# CtDPS_Stage.net
KiCad netlist of a schematic drawn in Altium Designer
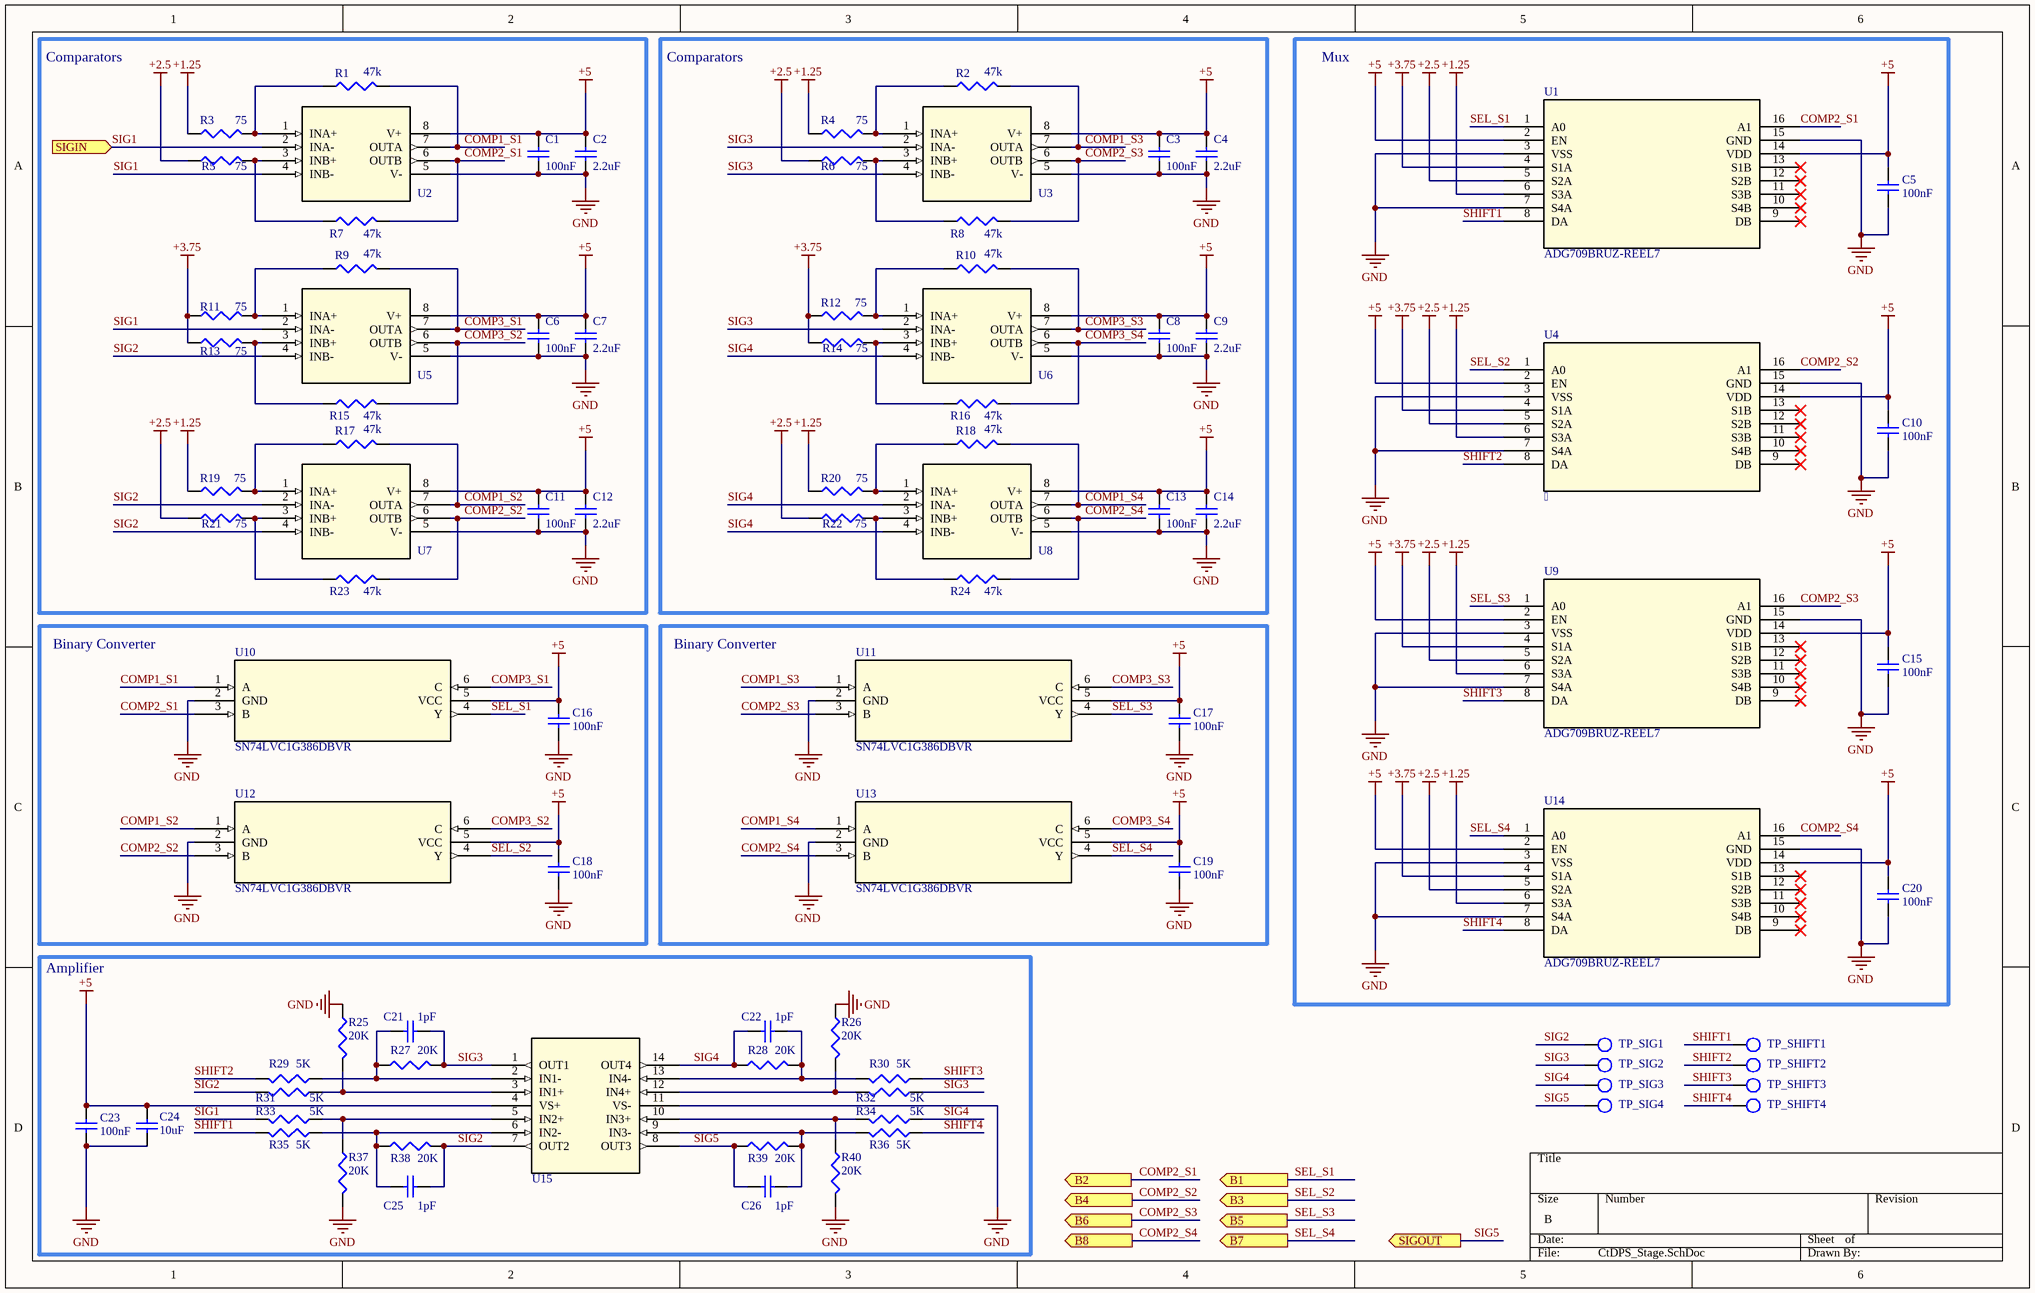
[diagram p0: CtDPS_Stage.SchDoc]

(export (version "E")
  (design (tool "Eeschema 10.0.6"))
  (components
    (comp (ref "C1")
      (value "100nF")
      (footprint "C_0402")
      (fields (field (name "LCSC PART #") "C1525"))
      (libsource (lib "ctdsp") (part "C_0402"))
    )
    (comp (ref "C2")
      (value "2.2uF")
      (footprint "C_0402")
      (fields (field (name "LCSC PART #") "C12530"))
      (libsource (lib "ctdsp") (part "C_0402"))
    )
    (comp (ref "C3")
      (value "100nF")
      (footprint "C_0402")
      (fields (field (name "LCSC PART #") "C1525"))
      (libsource (lib "ctdsp") (part "C_0402"))
    )
    (comp (ref "C4")
      (value "2.2uF")
      (footprint "C_0402")
      (fields (field (name "LCSC PART #") "C12530"))
      (libsource (lib "ctdsp") (part "C_0402"))
    )
    (comp (ref "C5")
      (value "100nF")
      (footprint "C_0402")
      (fields (field (name "LCSC PART #") "C1525"))
      (libsource (lib "ctdsp") (part "C_0402"))
    )
    (comp (ref "C6")
      (value "100nF")
      (footprint "C_0402")
      (fields (field (name "LCSC PART #") "C1525"))
      (libsource (lib "ctdsp") (part "C_0402"))
    )
    (comp (ref "C7")
      (value "2.2uF")
      (footprint "C_0402")
      (fields (field (name "LCSC PART #") "C12530"))
      (libsource (lib "ctdsp") (part "C_0402"))
    )
    (comp (ref "C8")
      (value "100nF")
      (footprint "C_0402")
      (fields (field (name "LCSC PART #") "C1525"))
      (libsource (lib "ctdsp") (part "C_0402"))
    )
    (comp (ref "C9")
      (value "2.2uF")
      (footprint "C_0402")
      (fields (field (name "LCSC PART #") "C12530"))
      (libsource (lib "ctdsp") (part "C_0402"))
    )
    (comp (ref "C10")
      (value "100nF")
      (footprint "C_0402")
      (fields (field (name "LCSC PART #") "C1525"))
      (libsource (lib "ctdsp") (part "C_0402"))
    )
    (comp (ref "C11")
      (value "100nF")
      (footprint "C_0402")
      (fields (field (name "LCSC PART #") "C1525"))
      (libsource (lib "ctdsp") (part "C_0402"))
    )
    (comp (ref "C12")
      (value "2.2uF")
      (footprint "C_0402")
      (fields (field (name "LCSC PART #") "C12530"))
      (libsource (lib "ctdsp") (part "C_0402"))
    )
    (comp (ref "C13")
      (value "100nF")
      (footprint "C_0402")
      (fields (field (name "LCSC PART #") "C1525"))
      (libsource (lib "ctdsp") (part "C_0402"))
    )
    (comp (ref "C14")
      (value "2.2uF")
      (footprint "C_0402")
      (fields (field (name "LCSC PART #") "C12530"))
      (libsource (lib "ctdsp") (part "C_0402"))
    )
    (comp (ref "C15")
      (value "100nF")
      (footprint "C_0402")
      (fields (field (name "LCSC PART #") "C1525"))
      (libsource (lib "ctdsp") (part "C_0402"))
    )
    (comp (ref "C16")
      (value "100nF")
      (footprint "C_0402")
      (fields (field (name "LCSC PART #") "C1525"))
      (libsource (lib "ctdsp") (part "C_0402"))
    )
    (comp (ref "C17")
      (value "100nF")
      (footprint "C_0402")
      (fields (field (name "LCSC PART #") "C1525"))
      (libsource (lib "ctdsp") (part "C_0402"))
    )
    (comp (ref "C18")
      (value "100nF")
      (footprint "C_0402")
      (fields (field (name "LCSC PART #") "C1525"))
      (libsource (lib "ctdsp") (part "C_0402"))
    )
    (comp (ref "C19")
      (value "100nF")
      (footprint "C_0402")
      (fields (field (name "LCSC PART #") "C1525"))
      (libsource (lib "ctdsp") (part "C_0402"))
    )
    (comp (ref "C20")
      (value "100nF")
      (footprint "C_0402")
      (fields (field (name "LCSC PART #") "C1525"))
      (libsource (lib "ctdsp") (part "C_0402"))
    )
    (comp (ref "C21")
      (value "1pF")
      (footprint "C_0402")
      (fields (field (name "LCSC PART #") "C1550"))
      (libsource (lib "ctdsp") (part "C_0402"))
    )
    (comp (ref "C22")
      (value "1pF")
      (footprint "C_0402")
      (fields (field (name "LCSC PART #") "C1550"))
      (libsource (lib "ctdsp") (part "C_0402"))
    )
    (comp (ref "C23")
      (value "100nF")
      (footprint "C_0402")
      (fields (field (name "LCSC PART #") "C1525"))
      (libsource (lib "ctdsp") (part "C_0402"))
    )
    (comp (ref "C24")
      (value "10uF")
      (footprint "C_0402")
      (fields (field (name "LCSC PART #") "C15525"))
      (libsource (lib "ctdsp") (part "C_0402"))
    )
    (comp (ref "C25")
      (value "1pF")
      (footprint "C_0402")
      (fields (field (name "LCSC PART #") "C1550"))
      (libsource (lib "ctdsp") (part "C_0402"))
    )
    (comp (ref "C26")
      (value "1pF")
      (footprint "C_0402")
      (fields (field (name "LCSC PART #") "C1550"))
      (libsource (lib "ctdsp") (part "C_0402"))
    )
    (comp (ref "R1")
      (value "47k")
      (footprint "RES_0603")
      (fields (field (name "LCSC PART #") "C25819"))
      (libsource (lib "ctdsp") (part "RES_0603"))
    )
    (comp (ref "R2")
      (value "47k")
      (footprint "RES_0603")
      (fields (field (name "LCSC PART #") "C25819"))
      (libsource (lib "ctdsp") (part "RES_0603"))
    )
    (comp (ref "R3")
      (value "75")
      (footprint "RES_0603")
      (fields (field (name "LCSC PART #") "C4275"))
      (libsource (lib "ctdsp") (part "RES_0603"))
    )
    (comp (ref "R4")
      (value "75")
      (footprint "RES_0603")
      (fields (field (name "LCSC PART #") "C4275"))
      (libsource (lib "ctdsp") (part "RES_0603"))
    )
    (comp (ref "R5")
      (value "75")
      (footprint "RES_0603")
      (fields (field (name "LCSC PART #") "C4275"))
      (libsource (lib "ctdsp") (part "RES_0603"))
    )
    (comp (ref "R6")
      (value "75")
      (footprint "RES_0603")
      (fields (field (name "LCSC PART #") "C4275"))
      (libsource (lib "ctdsp") (part "RES_0603"))
    )
    (comp (ref "R7")
      (value "47k")
      (footprint "RES_0603")
      (fields (field (name "LCSC PART #") "C25819"))
      (libsource (lib "ctdsp") (part "RES_0603"))
    )
    (comp (ref "R8")
      (value "47k")
      (footprint "RES_0603")
      (fields (field (name "LCSC PART #") "C25819"))
      (libsource (lib "ctdsp") (part "RES_0603"))
    )
    (comp (ref "R9")
      (value "47k")
      (footprint "RES_0603")
      (fields (field (name "LCSC PART #") "C25819"))
      (libsource (lib "ctdsp") (part "RES_0603"))
    )
    (comp (ref "R10")
      (value "47k")
      (footprint "RES_0603")
      (fields (field (name "LCSC PART #") "C25819"))
      (libsource (lib "ctdsp") (part "RES_0603"))
    )
    (comp (ref "R11")
      (value "75")
      (footprint "RES_0603")
      (fields (field (name "LCSC PART #") "C4275"))
      (libsource (lib "ctdsp") (part "RES_0603"))
    )
    (comp (ref "R12")
      (value "75")
      (footprint "RES_0603")
      (fields (field (name "LCSC PART #") "C4275"))
      (libsource (lib "ctdsp") (part "RES_0603"))
    )
    (comp (ref "R13")
      (value "75")
      (footprint "RES_0603")
      (fields (field (name "LCSC PART #") "C4275"))
      (libsource (lib "ctdsp") (part "RES_0603"))
    )
    (comp (ref "R14")
      (value "75")
      (footprint "RES_0603")
      (fields (field (name "LCSC PART #") "C4275"))
      (libsource (lib "ctdsp") (part "RES_0603"))
    )
    (comp (ref "R15")
      (value "47k")
      (footprint "RES_0603")
      (fields (field (name "LCSC PART #") "C25819"))
      (libsource (lib "ctdsp") (part "RES_0603"))
    )
    (comp (ref "R16")
      (value "47k")
      (footprint "RES_0603")
      (fields (field (name "LCSC PART #") "C25819"))
      (libsource (lib "ctdsp") (part "RES_0603"))
    )
    (comp (ref "R17")
      (value "47k")
      (footprint "RES_0603")
      (fields (field (name "LCSC PART #") "C25819"))
      (libsource (lib "ctdsp") (part "RES_0603"))
    )
    (comp (ref "R18")
      (value "47k")
      (footprint "RES_0603")
      (fields (field (name "LCSC PART #") "C25819"))
      (libsource (lib "ctdsp") (part "RES_0603"))
    )
    (comp (ref "R19")
      (value "75")
      (footprint "RES_0603")
      (fields (field (name "LCSC PART #") "C4275"))
      (libsource (lib "ctdsp") (part "RES_0603"))
    )
    (comp (ref "R20")
      (value "75")
      (footprint "RES_0603")
      (fields (field (name "LCSC PART #") "C4275"))
      (libsource (lib "ctdsp") (part "RES_0603"))
    )
    (comp (ref "R21")
      (value "75")
      (footprint "RES_0603")
      (fields (field (name "LCSC PART #") "C4275"))
      (libsource (lib "ctdsp") (part "RES_0603"))
    )
    (comp (ref "R22")
      (value "75")
      (footprint "RES_0603")
      (fields (field (name "LCSC PART #") "C4275"))
      (libsource (lib "ctdsp") (part "RES_0603"))
    )
    (comp (ref "R23")
      (value "47k")
      (footprint "RES_0603")
      (fields (field (name "LCSC PART #") "C25819"))
      (libsource (lib "ctdsp") (part "RES_0603"))
    )
    (comp (ref "R24")
      (value "47k")
      (footprint "RES_0603")
      (fields (field (name "LCSC PART #") "C25819"))
      (libsource (lib "ctdsp") (part "RES_0603"))
    )
    (comp (ref "R25")
      (value "20K")
      (footprint "RES_0402")
      (fields (field (name "LCSC PART #") "C25765"))
      (libsource (lib "ctdsp") (part "RES_0402"))
    )
    (comp (ref "R26")
      (value "20K")
      (footprint "RES_0402")
      (fields (field (name "LCSC PART #") "C25765"))
      (libsource (lib "ctdsp") (part "RES_0402"))
    )
    (comp (ref "R27")
      (value "20K")
      (footprint "RES_0402")
      (fields (field (name "LCSC PART #") "C25765"))
      (libsource (lib "ctdsp") (part "RES_0402"))
    )
    (comp (ref "R28")
      (value "20K")
      (footprint "RES_0402")
      (fields (field (name "LCSC PART #") "C25765"))
      (libsource (lib "ctdsp") (part "RES_0402"))
    )
    (comp (ref "R29")
      (value "5K")
      (footprint "RES_0402")
      (fields (field (name "LCSC PART #") "C5948099"))
      (libsource (lib "ctdsp") (part "RES_0402"))
    )
    (comp (ref "R30")
      (value "5K")
      (footprint "RES_0402")
      (fields (field (name "LCSC PART #") "C5948099"))
      (libsource (lib "ctdsp") (part "RES_0402"))
    )
    (comp (ref "R31")
      (value "5K")
      (footprint "RES_0402")
      (fields (field (name "LCSC PART #") "C5948099"))
      (libsource (lib "ctdsp") (part "RES_0402"))
    )
    (comp (ref "R32")
      (value "5K")
      (footprint "RES_0402")
      (fields (field (name "LCSC PART #") "C5948099"))
      (libsource (lib "ctdsp") (part "RES_0402"))
    )
    (comp (ref "R33")
      (value "5K")
      (footprint "RES_0402")
      (fields (field (name "LCSC PART #") "C5948099"))
      (libsource (lib "ctdsp") (part "RES_0402"))
    )
    (comp (ref "R34")
      (value "5K")
      (footprint "RES_0402")
      (fields (field (name "LCSC PART #") "C5948099"))
      (libsource (lib "ctdsp") (part "RES_0402"))
    )
    (comp (ref "R35")
      (value "5K")
      (footprint "RES_0402")
      (fields (field (name "LCSC PART #") "C5948099"))
      (libsource (lib "ctdsp") (part "RES_0402"))
    )
    (comp (ref "R36")
      (value "5K")
      (footprint "RES_0402")
      (fields (field (name "LCSC PART #") "C5948099"))
      (libsource (lib "ctdsp") (part "RES_0402"))
    )
    (comp (ref "R37")
      (value "20K")
      (footprint "RES_0402")
      (fields (field (name "LCSC PART #") "C25765"))
      (libsource (lib "ctdsp") (part "RES_0402"))
    )
    (comp (ref "R38")
      (value "20K")
      (footprint "RES_0402")
      (fields (field (name "LCSC PART #") "C25765"))
      (libsource (lib "ctdsp") (part "RES_0402"))
    )
    (comp (ref "R39")
      (value "20K")
      (footprint "RES_0402")
      (fields (field (name "LCSC PART #") "C25765"))
      (libsource (lib "ctdsp") (part "RES_0402"))
    )
    (comp (ref "R40")
      (value "20K")
      (footprint "RES_0402")
      (fields (field (name "LCSC PART #") "C25765"))
      (libsource (lib "ctdsp") (part "RES_0402"))
    )
    (comp (ref "TP_SHIFT1")
      (value "TESTPOINT")
      (footprint "TESTPOINT")
      (libsource (lib "ctdsp") (part "TESTPOINT"))
    )
    (comp (ref "TP_SHIFT2")
      (value "TESTPOINT")
      (footprint "TESTPOINT")
      (libsource (lib "ctdsp") (part "TESTPOINT"))
    )
    (comp (ref "TP_SHIFT3")
      (value "TESTPOINT")
      (footprint "TESTPOINT")
      (libsource (lib "ctdsp") (part "TESTPOINT"))
    )
    (comp (ref "TP_SHIFT4")
      (value "TESTPOINT")
      (footprint "TESTPOINT")
      (libsource (lib "ctdsp") (part "TESTPOINT"))
    )
    (comp (ref "TP_SIG1")
      (value "TESTPOINT")
      (footprint "TESTPOINT")
      (libsource (lib "ctdsp") (part "TESTPOINT"))
    )
    (comp (ref "TP_SIG2")
      (value "TESTPOINT")
      (footprint "TESTPOINT")
      (libsource (lib "ctdsp") (part "TESTPOINT"))
    )
    (comp (ref "TP_SIG3")
      (value "TESTPOINT")
      (footprint "TESTPOINT")
      (libsource (lib "ctdsp") (part "TESTPOINT"))
    )
    (comp (ref "TP_SIG4")
      (value "TESTPOINT")
      (footprint "TESTPOINT")
      (libsource (lib "ctdsp") (part "TESTPOINT"))
    )
    (comp (ref "U1")
      (value "ADG709BRUZ-REEL7")
      (footprint "ADG709BRUZ-REEL7")
      (description "CMOS Low Voltage, 3 Î© 4-Channel Multiplexer")
      (fields (field (name "LCSC PART #") "C206785"))
      (libsource (lib "ctdsp") (part "ADG709BRUZ-REEL7"))
    )
    (comp (ref "U2")
      (value "TLV3502AIDR")
      (footprint "TLV3502AIDR")
      (description "Dual 4.5ns Push-pull Rail-to-Rail Input, Rail-to-Rail Output TTL Comparators")
      (fields (field (name "LCSC PART #") "C131165"))
      (libsource (lib "ctdsp") (part "TLV3502AIDR"))
    )
    (comp (ref "U3")
      (value "TLV3502AIDR")
      (footprint "TLV3502AIDR")
      (description "Dual 4.5ns Push-pull Rail-to-Rail Input, Rail-to-Rail Output TTL Comparators")
      (fields (field (name "LCSC PART #") "C131165"))
      (libsource (lib "ctdsp") (part "TLV3502AIDR"))
    )
    (comp (ref "U4")
      (value "")
      (footprint "ADG709BRUZ-REEL7")
      (description "CMOS Low Voltage, 3 Î© 4-Channel Multiplexer")
      (fields (field (name "LCSC PART #") "C206785"))
      (libsource (lib "ctdsp") (part "ADG709BRUZ-REEL7"))
    )
    (comp (ref "U5")
      (value "TLV3502AIDR")
      (footprint "TLV3502AIDR")
      (description "Dual 4.5ns Push-pull Rail-to-Rail Input, Rail-to-Rail Output TTL Comparators")
      (fields (field (name "LCSC PART #") "C131165"))
      (libsource (lib "ctdsp") (part "TLV3502AIDR"))
    )
    (comp (ref "U6")
      (value "TLV3502AIDR")
      (footprint "TLV3502AIDR")
      (description "Dual 4.5ns Push-pull Rail-to-Rail Input, Rail-to-Rail Output TTL Comparators")
      (fields (field (name "LCSC PART #") "C131165"))
      (libsource (lib "ctdsp") (part "TLV3502AIDR"))
    )
    (comp (ref "U7")
      (value "TLV3502AIDR")
      (footprint "TLV3502AIDR")
      (description "Dual 4.5ns Push-pull Rail-to-Rail Input, Rail-to-Rail Output TTL Comparators")
      (fields (field (name "LCSC PART #") "C131165"))
      (libsource (lib "ctdsp") (part "TLV3502AIDR"))
    )
    (comp (ref "U8")
      (value "TLV3502AIDR")
      (footprint "TLV3502AIDR")
      (description "Dual 4.5ns Push-pull Rail-to-Rail Input, Rail-to-Rail Output TTL Comparators")
      (fields (field (name "LCSC PART #") "C131165"))
      (libsource (lib "ctdsp") (part "TLV3502AIDR"))
    )
    (comp (ref "U9")
      (value "ADG709BRUZ-REEL7")
      (footprint "ADG709BRUZ-REEL7")
      (description "CMOS Low Voltage, 3 Î© 4-Channel Multiplexer")
      (fields (field (name "LCSC PART #") "C206785"))
      (libsource (lib "ctdsp") (part "ADG709BRUZ-REEL7"))
    )
    (comp (ref "U10")
      (value "SN74LVC1G386DBVR")
      (footprint "SN74LVC1G386DBVR")
      (description "Single 3-input, 1.65-V to 5.5-V XOR (exclusive OR) gate 6-SOT-23 -40 to 125")
      (fields (field (name "LCSC PART #") "C2838503"))
      (libsource (lib "ctdsp") (part "SN74LVC1G386DBVR"))
    )
    (comp (ref "U11")
      (value "SN74LVC1G386DBVR")
      (footprint "SN74LVC1G386DBVR")
      (description "Single 3-input, 1.65-V to 5.5-V XOR (exclusive OR) gate 6-SOT-23 -40 to 125")
      (fields (field (name "LCSC PART #") "C2838503"))
      (libsource (lib "ctdsp") (part "SN74LVC1G386DBVR"))
    )
    (comp (ref "U12")
      (value "SN74LVC1G386DBVR")
      (footprint "SN74LVC1G386DBVR")
      (description "Single 3-input, 1.65-V to 5.5-V XOR (exclusive OR) gate 6-SOT-23 -40 to 125")
      (fields (field (name "LCSC PART #") "C2838503"))
      (libsource (lib "ctdsp") (part "SN74LVC1G386DBVR"))
    )
    (comp (ref "U13")
      (value "SN74LVC1G386DBVR")
      (footprint "SN74LVC1G386DBVR")
      (description "Single 3-input, 1.65-V to 5.5-V XOR (exclusive OR) gate 6-SOT-23 -40 to 125")
      (fields (field (name "LCSC PART #") "C2838503"))
      (libsource (lib "ctdsp") (part "SN74LVC1G386DBVR"))
    )
    (comp (ref "U14")
      (value "ADG709BRUZ-REEL7")
      (footprint "ADG709BRUZ-REEL7")
      (description "CMOS Low Voltage, 3 Î© 4-Channel Multiplexer")
      (fields (field (name "LCSC PART #") "C206785"))
      (libsource (lib "ctdsp") (part "ADG709BRUZ-REEL7"))
    )
    (comp (ref "U15")
      (value "ADA4891-4ARZ-R7")
      (footprint "ADA4891-4ARZ-R7")
      (description "Quad Rail-to-Rail Op-Amp, 240 MHz, 170 V/µs, SOT-23-5")
      (fields (field (name "LCSC PART #") "C654290"))
      (libsource (lib "ctdsp") (part "ADA4891-4ARZ-R7"))
    )
  )
  (nets
    (net (code "1") (name "+1.25") (class "Default")
      (node (ref "R19") (pin "1") (pinfunction "1_1") (pintype "passive"))
      (node (ref "R20") (pin "1") (pinfunction "1_1") (pintype "passive"))
      (node (ref "R3") (pin "1") (pinfunction "1_1") (pintype "passive"))
      (node (ref "R4") (pin "1") (pinfunction "1_1") (pintype "passive"))
      (node (ref "U1") (pin "6") (pinfunction "S3A_6") (pintype "passive"))
      (node (ref "U14") (pin "6") (pinfunction "S3A_6") (pintype "passive"))
      (node (ref "U4") (pin "6") (pinfunction "S3A_6") (pintype "passive"))
      (node (ref "U9") (pin "6") (pinfunction "S3A_6") (pintype "passive"))
    )
    (net (code "2") (name "+2.5") (class "Default")
      (node (ref "R21") (pin "1") (pinfunction "1_1") (pintype "passive"))
      (node (ref "R22") (pin "1") (pinfunction "1_1") (pintype "passive"))
      (node (ref "R5") (pin "1") (pinfunction "1_1") (pintype "passive"))
      (node (ref "R6") (pin "1") (pinfunction "1_1") (pintype "passive"))
      (node (ref "U1") (pin "5") (pinfunction "S2A_5") (pintype "passive"))
      (node (ref "U14") (pin "5") (pinfunction "S2A_5") (pintype "passive"))
      (node (ref "U4") (pin "5") (pinfunction "S2A_5") (pintype "passive"))
      (node (ref "U9") (pin "5") (pinfunction "S2A_5") (pintype "passive"))
    )
    (net (code "3") (name "+3.75") (class "Default")
      (node (ref "R11") (pin "1") (pinfunction "1_1") (pintype "passive"))
      (node (ref "R12") (pin "1") (pinfunction "1_1") (pintype "passive"))
      (node (ref "R13") (pin "1") (pinfunction "1_1") (pintype "passive"))
      (node (ref "R14") (pin "1") (pinfunction "1_1") (pintype "passive"))
      (node (ref "U1") (pin "4") (pinfunction "S1A_4") (pintype "passive"))
      (node (ref "U14") (pin "4") (pinfunction "S1A_4") (pintype "passive"))
      (node (ref "U4") (pin "4") (pinfunction "S1A_4") (pintype "passive"))
      (node (ref "U9") (pin "4") (pinfunction "S1A_4") (pintype "passive"))
    )
    (net (code "4") (name "+5") (class "Default")
      (node (ref "C1") (pin "1") (pinfunction "1_1") (pintype "passive"))
      (node (ref "C10") (pin "1") (pinfunction "1_1") (pintype "passive"))
      (node (ref "C11") (pin "1") (pinfunction "1_1") (pintype "passive"))
      (node (ref "C12") (pin "2") (pinfunction "2_2") (pintype "passive"))
      (node (ref "C13") (pin "1") (pinfunction "1_1") (pintype "passive"))
      (node (ref "C14") (pin "2") (pinfunction "2_2") (pintype "passive"))
      (node (ref "C15") (pin "1") (pinfunction "1_1") (pintype "passive"))
      (node (ref "C16") (pin "1") (pinfunction "1_1") (pintype "passive"))
      (node (ref "C17") (pin "1") (pinfunction "1_1") (pintype "passive"))
      (node (ref "C18") (pin "1") (pinfunction "1_1") (pintype "passive"))
      (node (ref "C19") (pin "1") (pinfunction "1_1") (pintype "passive"))
      (node (ref "C2") (pin "2") (pinfunction "2_2") (pintype "passive"))
      (node (ref "C20") (pin "1") (pinfunction "1_1") (pintype "passive"))
      (node (ref "C23") (pin "1") (pinfunction "1_1") (pintype "passive"))
      (node (ref "C24") (pin "2") (pinfunction "2_2") (pintype "passive"))
      (node (ref "C3") (pin "1") (pinfunction "1_1") (pintype "passive"))
      (node (ref "C4") (pin "2") (pinfunction "2_2") (pintype "passive"))
      (node (ref "C5") (pin "1") (pinfunction "1_1") (pintype "passive"))
      (node (ref "C6") (pin "1") (pinfunction "1_1") (pintype "passive"))
      (node (ref "C7") (pin "2") (pinfunction "2_2") (pintype "passive"))
      (node (ref "C8") (pin "1") (pinfunction "1_1") (pintype "passive"))
      (node (ref "C9") (pin "2") (pinfunction "2_2") (pintype "passive"))
      (node (ref "U1") (pin "14") (pinfunction "VDD_14") (pintype "power_in"))
      (node (ref "U1") (pin "2") (pinfunction "EN_2") (pintype "passive"))
      (node (ref "U10") (pin "5") (pinfunction "VCC_5") (pintype "power_in"))
      (node (ref "U11") (pin "5") (pinfunction "VCC_5") (pintype "power_in"))
      (node (ref "U12") (pin "5") (pinfunction "VCC_5") (pintype "power_in"))
      (node (ref "U13") (pin "5") (pinfunction "VCC_5") (pintype "power_in"))
      (node (ref "U14") (pin "14") (pinfunction "VDD_14") (pintype "power_in"))
      (node (ref "U14") (pin "2") (pinfunction "EN_2") (pintype "passive"))
      (node (ref "U15") (pin "4") (pinfunction "VS+_4") (pintype "power_in"))
      (node (ref "U2") (pin "8") (pinfunction "V+_8") (pintype "power_in"))
      (node (ref "U3") (pin "8") (pinfunction "V+_8") (pintype "power_in"))
      (node (ref "U4") (pin "14") (pinfunction "VDD_14") (pintype "power_in"))
      (node (ref "U4") (pin "2") (pinfunction "EN_2") (pintype "passive"))
      (node (ref "U5") (pin "8") (pinfunction "V+_8") (pintype "power_in"))
      (node (ref "U6") (pin "8") (pinfunction "V+_8") (pintype "power_in"))
      (node (ref "U7") (pin "8") (pinfunction "V+_8") (pintype "power_in"))
      (node (ref "U8") (pin "8") (pinfunction "V+_8") (pintype "power_in"))
      (node (ref "U9") (pin "14") (pinfunction "VDD_14") (pintype "power_in"))
      (node (ref "U9") (pin "2") (pinfunction "EN_2") (pintype "passive"))
    )
    (net (code "5") (name "/COMP1_S1") (class "Default")
      (node (ref "R1") (pin "2") (pinfunction "2_2") (pintype "passive"))
      (node (ref "U10") (pin "1") (pinfunction "A_1") (pintype "input"))
      (node (ref "U2") (pin "7") (pinfunction "OUTA_7") (pintype "output"))
    )
    (net (code "6") (name "/COMP1_S2") (class "Default")
      (node (ref "R17") (pin "2") (pinfunction "2_2") (pintype "passive"))
      (node (ref "U12") (pin "1") (pinfunction "A_1") (pintype "input"))
      (node (ref "U7") (pin "7") (pinfunction "OUTA_7") (pintype "output"))
    )
    (net (code "7") (name "/COMP1_S3") (class "Default")
      (node (ref "R2") (pin "2") (pinfunction "2_2") (pintype "passive"))
      (node (ref "U11") (pin "1") (pinfunction "A_1") (pintype "input"))
      (node (ref "U3") (pin "7") (pinfunction "OUTA_7") (pintype "output"))
    )
    (net (code "8") (name "/COMP1_S4") (class "Default")
      (node (ref "R18") (pin "2") (pinfunction "2_2") (pintype "passive"))
      (node (ref "U13") (pin "1") (pinfunction "A_1") (pintype "input"))
      (node (ref "U8") (pin "7") (pinfunction "OUTA_7") (pintype "output"))
    )
    (net (code "9") (name "/COMP2_S1") (class "Default")
      (node (ref "R7") (pin "2") (pinfunction "2_2") (pintype "passive"))
      (node (ref "U1") (pin "16") (pinfunction "A1_16") (pintype "passive"))
      (node (ref "U10") (pin "3") (pinfunction "B_3") (pintype "input"))
      (node (ref "U2") (pin "6") (pinfunction "OUTB_6") (pintype "output"))
    )
    (net (code "10") (name "/COMP2_S2") (class "Default")
      (node (ref "R23") (pin "2") (pinfunction "2_2") (pintype "passive"))
      (node (ref "U12") (pin "3") (pinfunction "B_3") (pintype "input"))
      (node (ref "U4") (pin "16") (pinfunction "A1_16") (pintype "passive"))
      (node (ref "U7") (pin "6") (pinfunction "OUTB_6") (pintype "output"))
    )
    (net (code "11") (name "/COMP2_S3") (class "Default")
      (node (ref "R8") (pin "2") (pinfunction "2_2") (pintype "passive"))
      (node (ref "U11") (pin "3") (pinfunction "B_3") (pintype "input"))
      (node (ref "U3") (pin "6") (pinfunction "OUTB_6") (pintype "output"))
      (node (ref "U9") (pin "16") (pinfunction "A1_16") (pintype "passive"))
    )
    (net (code "12") (name "/COMP2_S4") (class "Default")
      (node (ref "R24") (pin "2") (pinfunction "2_2") (pintype "passive"))
      (node (ref "U13") (pin "3") (pinfunction "B_3") (pintype "input"))
      (node (ref "U14") (pin "16") (pinfunction "A1_16") (pintype "passive"))
      (node (ref "U8") (pin "6") (pinfunction "OUTB_6") (pintype "output"))
    )
    (net (code "13") (name "/COMP3_S1") (class "Default")
      (node (ref "R9") (pin "2") (pinfunction "2_2") (pintype "passive"))
      (node (ref "U10") (pin "6") (pinfunction "C_6") (pintype "input"))
      (node (ref "U5") (pin "7") (pinfunction "OUTA_7") (pintype "output"))
    )
    (net (code "14") (name "/COMP3_S2") (class "Default")
      (node (ref "R15") (pin "2") (pinfunction "2_2") (pintype "passive"))
      (node (ref "U12") (pin "6") (pinfunction "C_6") (pintype "input"))
      (node (ref "U5") (pin "6") (pinfunction "OUTB_6") (pintype "output"))
    )
    (net (code "15") (name "/COMP3_S3") (class "Default")
      (node (ref "R10") (pin "2") (pinfunction "2_2") (pintype "passive"))
      (node (ref "U11") (pin "6") (pinfunction "C_6") (pintype "input"))
      (node (ref "U6") (pin "7") (pinfunction "OUTA_7") (pintype "output"))
    )
    (net (code "16") (name "/COMP3_S4") (class "Default")
      (node (ref "R16") (pin "2") (pinfunction "2_2") (pintype "passive"))
      (node (ref "U13") (pin "6") (pinfunction "C_6") (pintype "input"))
      (node (ref "U6") (pin "6") (pinfunction "OUTB_6") (pintype "output"))
    )
    (net (code "17") (name "/SEL_S1") (class "Default")
      (node (ref "U1") (pin "1") (pinfunction "A0_1") (pintype "passive"))
      (node (ref "U10") (pin "4") (pinfunction "Y_4") (pintype "output"))
    )
    (net (code "18") (name "/SEL_S2") (class "Default")
      (node (ref "U12") (pin "4") (pinfunction "Y_4") (pintype "output"))
      (node (ref "U4") (pin "1") (pinfunction "A0_1") (pintype "passive"))
    )
    (net (code "19") (name "/SEL_S3") (class "Default")
      (node (ref "U11") (pin "4") (pinfunction "Y_4") (pintype "output"))
      (node (ref "U9") (pin "1") (pinfunction "A0_1") (pintype "passive"))
    )
    (net (code "20") (name "/SEL_S4") (class "Default")
      (node (ref "U13") (pin "4") (pinfunction "Y_4") (pintype "output"))
      (node (ref "U14") (pin "1") (pinfunction "A0_1") (pintype "passive"))
    )
    (net (code "21") (name "/SHIFT1") (class "Default")
      (node (ref "R35") (pin "1") (pinfunction "1_1") (pintype "passive"))
      (node (ref "TP_SHIFT1") (pin "1") (pinfunction "1_1") (pintype "passive"))
      (node (ref "U1") (pin "8") (pinfunction "DA_8") (pintype "passive"))
    )
    (net (code "22") (name "/SHIFT2") (class "Default")
      (node (ref "R29") (pin "1") (pinfunction "1_1") (pintype "passive"))
      (node (ref "TP_SHIFT2") (pin "1") (pinfunction "1_1") (pintype "passive"))
      (node (ref "U4") (pin "8") (pinfunction "DA_8") (pintype "passive"))
    )
    (net (code "23") (name "/SHIFT3") (class "Default")
      (node (ref "R30") (pin "2") (pinfunction "2_2") (pintype "passive"))
      (node (ref "TP_SHIFT3") (pin "1") (pinfunction "1_1") (pintype "passive"))
      (node (ref "U9") (pin "8") (pinfunction "DA_8") (pintype "passive"))
    )
    (net (code "24") (name "/SHIFT4") (class "Default")
      (node (ref "R36") (pin "2") (pinfunction "2_2") (pintype "passive"))
      (node (ref "TP_SHIFT4") (pin "1") (pinfunction "1_1") (pintype "passive"))
      (node (ref "U14") (pin "8") (pinfunction "DA_8") (pintype "passive"))
    )
    (net (code "25") (name "/SIG1") (class "Default")
      (node (ref "R33") (pin "1") (pinfunction "1_1") (pintype "passive"))
      (node (ref "U2") (pin "2") (pinfunction "INA-_2") (pintype "input"))
      (node (ref "U2") (pin "4") (pinfunction "INB-_4") (pintype "input"))
      (node (ref "U5") (pin "2") (pinfunction "INA-_2") (pintype "input"))
    )
    (net (code "26") (name "/SIG2") (class "Default")
      (node (ref "C25") (pin "2") (pinfunction "2_2") (pintype "passive"))
      (node (ref "R31") (pin "1") (pinfunction "1_1") (pintype "passive"))
      (node (ref "R38") (pin "2") (pinfunction "2_2") (pintype "passive"))
      (node (ref "TP_SIG1") (pin "1") (pinfunction "1_1") (pintype "passive"))
      (node (ref "U15") (pin "7") (pinfunction "OUT2_7") (pintype "output"))
      (node (ref "U5") (pin "4") (pinfunction "INB-_4") (pintype "input"))
      (node (ref "U7") (pin "2") (pinfunction "INA-_2") (pintype "input"))
      (node (ref "U7") (pin "4") (pinfunction "INB-_4") (pintype "input"))
    )
    (net (code "27") (name "/SIG3") (class "Default")
      (node (ref "C21") (pin "2") (pinfunction "2_2") (pintype "passive"))
      (node (ref "R27") (pin "2") (pinfunction "2_2") (pintype "passive"))
      (node (ref "R32") (pin "2") (pinfunction "2_2") (pintype "passive"))
      (node (ref "TP_SIG2") (pin "1") (pinfunction "1_1") (pintype "passive"))
      (node (ref "U15") (pin "1") (pinfunction "OUT1_1") (pintype "output"))
      (node (ref "U3") (pin "2") (pinfunction "INA-_2") (pintype "input"))
      (node (ref "U3") (pin "4") (pinfunction "INB-_4") (pintype "input"))
      (node (ref "U6") (pin "2") (pinfunction "INA-_2") (pintype "input"))
    )
    (net (code "28") (name "/SIG4") (class "Default")
      (node (ref "C22") (pin "1") (pinfunction "1_1") (pintype "passive"))
      (node (ref "R28") (pin "1") (pinfunction "1_1") (pintype "passive"))
      (node (ref "R34") (pin "2") (pinfunction "2_2") (pintype "passive"))
      (node (ref "TP_SIG3") (pin "1") (pinfunction "1_1") (pintype "passive"))
      (node (ref "U15") (pin "14") (pinfunction "OUT4_14") (pintype "output"))
      (node (ref "U6") (pin "4") (pinfunction "INB-_4") (pintype "input"))
      (node (ref "U8") (pin "2") (pinfunction "INA-_2") (pintype "input"))
      (node (ref "U8") (pin "4") (pinfunction "INB-_4") (pintype "input"))
    )
    (net (code "29") (name "/SIG5") (class "Default")
      (node (ref "C26") (pin "1") (pinfunction "1_1") (pintype "passive"))
      (node (ref "R39") (pin "1") (pinfunction "1_1") (pintype "passive"))
      (node (ref "TP_SIG4") (pin "1") (pinfunction "1_1") (pintype "passive"))
      (node (ref "U15") (pin "8") (pinfunction "OUT3_8") (pintype "output"))
    )
    (net (code "30") (name "GND") (class "Default")
      (node (ref "C1") (pin "2") (pinfunction "2_2") (pintype "passive"))
      (node (ref "C10") (pin "2") (pinfunction "2_2") (pintype "passive"))
      (node (ref "C11") (pin "2") (pinfunction "2_2") (pintype "passive"))
      (node (ref "C12") (pin "1") (pinfunction "1_1") (pintype "passive"))
      (node (ref "C13") (pin "2") (pinfunction "2_2") (pintype "passive"))
      (node (ref "C14") (pin "1") (pinfunction "1_1") (pintype "passive"))
      (node (ref "C15") (pin "2") (pinfunction "2_2") (pintype "passive"))
      (node (ref "C16") (pin "2") (pinfunction "2_2") (pintype "passive"))
      (node (ref "C17") (pin "2") (pinfunction "2_2") (pintype "passive"))
      (node (ref "C18") (pin "2") (pinfunction "2_2") (pintype "passive"))
      (node (ref "C19") (pin "2") (pinfunction "2_2") (pintype "passive"))
      (node (ref "C2") (pin "1") (pinfunction "1_1") (pintype "passive"))
      (node (ref "C20") (pin "2") (pinfunction "2_2") (pintype "passive"))
      (node (ref "C23") (pin "2") (pinfunction "2_2") (pintype "passive"))
      (node (ref "C24") (pin "1") (pinfunction "1_1") (pintype "passive"))
      (node (ref "C3") (pin "2") (pinfunction "2_2") (pintype "passive"))
      (node (ref "C4") (pin "1") (pinfunction "1_1") (pintype "passive"))
      (node (ref "C5") (pin "2") (pinfunction "2_2") (pintype "passive"))
      (node (ref "C6") (pin "2") (pinfunction "2_2") (pintype "passive"))
      (node (ref "C7") (pin "1") (pinfunction "1_1") (pintype "passive"))
      (node (ref "C8") (pin "2") (pinfunction "2_2") (pintype "passive"))
      (node (ref "C9") (pin "1") (pinfunction "1_1") (pintype "passive"))
      (node (ref "R25") (pin "1") (pinfunction "1_1") (pintype "passive"))
      (node (ref "R26") (pin "1") (pinfunction "1_1") (pintype "passive"))
      (node (ref "R37") (pin "2") (pinfunction "2_2") (pintype "passive"))
      (node (ref "R40") (pin "2") (pinfunction "2_2") (pintype "passive"))
      (node (ref "U1") (pin "15") (pinfunction "GND_15") (pintype "passive"))
      (node (ref "U1") (pin "3") (pinfunction "VSS_3") (pintype "power_in"))
      (node (ref "U1") (pin "7") (pinfunction "S4A_7") (pintype "passive"))
      (node (ref "U10") (pin "2") (pinfunction "GND_2") (pintype "power_in"))
      (node (ref "U11") (pin "2") (pinfunction "GND_2") (pintype "power_in"))
      (node (ref "U12") (pin "2") (pinfunction "GND_2") (pintype "power_in"))
      (node (ref "U13") (pin "2") (pinfunction "GND_2") (pintype "power_in"))
      (node (ref "U14") (pin "15") (pinfunction "GND_15") (pintype "passive"))
      (node (ref "U14") (pin "3") (pinfunction "VSS_3") (pintype "power_in"))
      (node (ref "U14") (pin "7") (pinfunction "S4A_7") (pintype "passive"))
      (node (ref "U15") (pin "11") (pinfunction "VS-_11") (pintype "power_in"))
      (node (ref "U2") (pin "5") (pinfunction "V-_5") (pintype "power_in"))
      (node (ref "U3") (pin "5") (pinfunction "V-_5") (pintype "power_in"))
      (node (ref "U4") (pin "15") (pinfunction "GND_15") (pintype "passive"))
      (node (ref "U4") (pin "3") (pinfunction "VSS_3") (pintype "power_in"))
      (node (ref "U4") (pin "7") (pinfunction "S4A_7") (pintype "passive"))
      (node (ref "U5") (pin "5") (pinfunction "V-_5") (pintype "power_in"))
      (node (ref "U6") (pin "5") (pinfunction "V-_5") (pintype "power_in"))
      (node (ref "U7") (pin "5") (pinfunction "V-_5") (pintype "power_in"))
      (node (ref "U8") (pin "5") (pinfunction "V-_5") (pintype "power_in"))
      (node (ref "U9") (pin "15") (pinfunction "GND_15") (pintype "passive"))
      (node (ref "U9") (pin "3") (pinfunction "VSS_3") (pintype "power_in"))
      (node (ref "U9") (pin "7") (pinfunction "S4A_7") (pintype "passive"))
    )
    (net (code "31") (name "Net-(U2-INA+)") (class "Default")
      (node (ref "R1") (pin "1") (pinfunction "1_1") (pintype "passive"))
      (node (ref "R3") (pin "2") (pinfunction "2_2") (pintype "passive"))
      (node (ref "U2") (pin "1") (pinfunction "INA+_1") (pintype "input"))
    )
    (net (code "32") (name "Net-(U2-INB+)") (class "Default")
      (node (ref "R5") (pin "2") (pinfunction "2_2") (pintype "passive"))
      (node (ref "R7") (pin "1") (pinfunction "1_1") (pintype "passive"))
      (node (ref "U2") (pin "3") (pinfunction "INB+_3") (pintype "input"))
    )
    (net (code "33") (name "Net-(U3-INA+)") (class "Default")
      (node (ref "R2") (pin "1") (pinfunction "1_1") (pintype "passive"))
      (node (ref "R4") (pin "2") (pinfunction "2_2") (pintype "passive"))
      (node (ref "U3") (pin "1") (pinfunction "INA+_1") (pintype "input"))
    )
    (net (code "34") (name "Net-(U3-INB+)") (class "Default")
      (node (ref "R6") (pin "2") (pinfunction "2_2") (pintype "passive"))
      (node (ref "R8") (pin "1") (pinfunction "1_1") (pintype "passive"))
      (node (ref "U3") (pin "3") (pinfunction "INB+_3") (pintype "input"))
    )
    (net (code "35") (name "Net-(U5-INA+)") (class "Default")
      (node (ref "R11") (pin "2") (pinfunction "2_2") (pintype "passive"))
      (node (ref "R9") (pin "1") (pinfunction "1_1") (pintype "passive"))
      (node (ref "U5") (pin "1") (pinfunction "INA+_1") (pintype "input"))
    )
    (net (code "36") (name "Net-(U5-INB+)") (class "Default")
      (node (ref "R13") (pin "2") (pinfunction "2_2") (pintype "passive"))
      (node (ref "R15") (pin "1") (pinfunction "1_1") (pintype "passive"))
      (node (ref "U5") (pin "3") (pinfunction "INB+_3") (pintype "input"))
    )
    (net (code "37") (name "Net-(U6-INA+)") (class "Default")
      (node (ref "R10") (pin "1") (pinfunction "1_1") (pintype "passive"))
      (node (ref "R12") (pin "2") (pinfunction "2_2") (pintype "passive"))
      (node (ref "U6") (pin "1") (pinfunction "INA+_1") (pintype "input"))
    )
    (net (code "38") (name "Net-(U6-INB+)") (class "Default")
      (node (ref "R14") (pin "2") (pinfunction "2_2") (pintype "passive"))
      (node (ref "R16") (pin "1") (pinfunction "1_1") (pintype "passive"))
      (node (ref "U6") (pin "3") (pinfunction "INB+_3") (pintype "input"))
    )
    (net (code "39") (name "Net-(U7-INA+)") (class "Default")
      (node (ref "R17") (pin "1") (pinfunction "1_1") (pintype "passive"))
      (node (ref "R19") (pin "2") (pinfunction "2_2") (pintype "passive"))
      (node (ref "U7") (pin "1") (pinfunction "INA+_1") (pintype "input"))
    )
    (net (code "40") (name "Net-(U7-INB+)") (class "Default")
      (node (ref "R21") (pin "2") (pinfunction "2_2") (pintype "passive"))
      (node (ref "R23") (pin "1") (pinfunction "1_1") (pintype "passive"))
      (node (ref "U7") (pin "3") (pinfunction "INB+_3") (pintype "input"))
    )
    (net (code "41") (name "Net-(U8-INA+)") (class "Default")
      (node (ref "R18") (pin "1") (pinfunction "1_1") (pintype "passive"))
      (node (ref "R20") (pin "2") (pinfunction "2_2") (pintype "passive"))
      (node (ref "U8") (pin "1") (pinfunction "INA+_1") (pintype "input"))
    )
    (net (code "42") (name "Net-(U8-INB+)") (class "Default")
      (node (ref "R22") (pin "2") (pinfunction "2_2") (pintype "passive"))
      (node (ref "R24") (pin "1") (pinfunction "1_1") (pintype "passive"))
      (node (ref "U8") (pin "3") (pinfunction "INB+_3") (pintype "input"))
    )
    (net (code "43") (name "Net-(U15-IN1+)") (class "Default")
      (node (ref "R25") (pin "2") (pinfunction "2_2") (pintype "passive"))
      (node (ref "R31") (pin "2") (pinfunction "2_2") (pintype "passive"))
      (node (ref "U15") (pin "3") (pinfunction "IN1+_3") (pintype "input"))
    )
    (net (code "44") (name "Net-(U15-IN1-)") (class "Default")
      (node (ref "C21") (pin "1") (pinfunction "1_1") (pintype "passive"))
      (node (ref "R27") (pin "1") (pinfunction "1_1") (pintype "passive"))
      (node (ref "R29") (pin "2") (pinfunction "2_2") (pintype "passive"))
      (node (ref "U15") (pin "2") (pinfunction "IN1-_2") (pintype "input"))
    )
    (net (code "45") (name "Net-(U15-IN2+)") (class "Default")
      (node (ref "R33") (pin "2") (pinfunction "2_2") (pintype "passive"))
      (node (ref "R37") (pin "1") (pinfunction "1_1") (pintype "passive"))
      (node (ref "U15") (pin "5") (pinfunction "IN2+_5") (pintype "input"))
    )
    (net (code "46") (name "Net-(U15-IN2-)") (class "Default")
      (node (ref "C25") (pin "1") (pinfunction "1_1") (pintype "passive"))
      (node (ref "R35") (pin "2") (pinfunction "2_2") (pintype "passive"))
      (node (ref "R38") (pin "1") (pinfunction "1_1") (pintype "passive"))
      (node (ref "U15") (pin "6") (pinfunction "IN2-_6") (pintype "input"))
    )
    (net (code "47") (name "Net-(U15-IN3+)") (class "Default")
      (node (ref "R34") (pin "1") (pinfunction "1_1") (pintype "passive"))
      (node (ref "R40") (pin "1") (pinfunction "1_1") (pintype "passive"))
      (node (ref "U15") (pin "10") (pinfunction "IN3+_10") (pintype "input"))
    )
    (net (code "48") (name "Net-(U15-IN3-)") (class "Default")
      (node (ref "C26") (pin "2") (pinfunction "2_2") (pintype "passive"))
      (node (ref "R36") (pin "1") (pinfunction "1_1") (pintype "passive"))
      (node (ref "R39") (pin "2") (pinfunction "2_2") (pintype "passive"))
      (node (ref "U15") (pin "9") (pinfunction "IN3-_9") (pintype "input"))
    )
    (net (code "49") (name "Net-(U15-IN4+)") (class "Default")
      (node (ref "R26") (pin "2") (pinfunction "2_2") (pintype "passive"))
      (node (ref "R32") (pin "1") (pinfunction "1_1") (pintype "passive"))
      (node (ref "U15") (pin "12") (pinfunction "IN4+_12") (pintype "input"))
    )
    (net (code "50") (name "Net-(U15-IN4-)") (class "Default")
      (node (ref "C22") (pin "2") (pinfunction "2_2") (pintype "passive"))
      (node (ref "R28") (pin "2") (pinfunction "2_2") (pintype "passive"))
      (node (ref "R30") (pin "1") (pinfunction "1_1") (pintype "passive"))
      (node (ref "U15") (pin "13") (pinfunction "IN4-_13") (pintype "input"))
    )
    (net (code "51") (name "unconnected-(U1-DB-Pad9)") (class "Default")
      (node (ref "U1") (pin "9") (pinfunction "DB_9") (pintype "passive+no_connect"))
    )
    (net (code "52") (name "unconnected-(U1-S1B-Pad13)") (class "Default")
      (node (ref "U1") (pin "13") (pinfunction "S1B_13") (pintype "passive+no_connect"))
    )
    (net (code "53") (name "unconnected-(U1-S2B-Pad12)") (class "Default")
      (node (ref "U1") (pin "12") (pinfunction "S2B_12") (pintype "passive+no_connect"))
    )
    (net (code "54") (name "unconnected-(U1-S3B-Pad11)") (class "Default")
      (node (ref "U1") (pin "11") (pinfunction "S3B_11") (pintype "passive+no_connect"))
    )
    (net (code "55") (name "unconnected-(U1-S4B-Pad10)") (class "Default")
      (node (ref "U1") (pin "10") (pinfunction "S4B_10") (pintype "passive+no_connect"))
    )
    (net (code "56") (name "unconnected-(U4-DB-Pad9)") (class "Default")
      (node (ref "U4") (pin "9") (pinfunction "DB_9") (pintype "passive+no_connect"))
    )
    (net (code "57") (name "unconnected-(U4-S1B-Pad13)") (class "Default")
      (node (ref "U4") (pin "13") (pinfunction "S1B_13") (pintype "passive+no_connect"))
    )
    (net (code "58") (name "unconnected-(U4-S2B-Pad12)") (class "Default")
      (node (ref "U4") (pin "12") (pinfunction "S2B_12") (pintype "passive+no_connect"))
    )
    (net (code "59") (name "unconnected-(U4-S3B-Pad11)") (class "Default")
      (node (ref "U4") (pin "11") (pinfunction "S3B_11") (pintype "passive+no_connect"))
    )
    (net (code "60") (name "unconnected-(U4-S4B-Pad10)") (class "Default")
      (node (ref "U4") (pin "10") (pinfunction "S4B_10") (pintype "passive+no_connect"))
    )
    (net (code "61") (name "unconnected-(U9-DB-Pad9)") (class "Default")
      (node (ref "U9") (pin "9") (pinfunction "DB_9") (pintype "passive+no_connect"))
    )
    (net (code "62") (name "unconnected-(U9-S1B-Pad13)") (class "Default")
      (node (ref "U9") (pin "13") (pinfunction "S1B_13") (pintype "passive+no_connect"))
    )
    (net (code "63") (name "unconnected-(U9-S2B-Pad12)") (class "Default")
      (node (ref "U9") (pin "12") (pinfunction "S2B_12") (pintype "passive+no_connect"))
    )
    (net (code "64") (name "unconnected-(U9-S3B-Pad11)") (class "Default")
      (node (ref "U9") (pin "11") (pinfunction "S3B_11") (pintype "passive+no_connect"))
    )
    (net (code "65") (name "unconnected-(U9-S4B-Pad10)") (class "Default")
      (node (ref "U9") (pin "10") (pinfunction "S4B_10") (pintype "passive+no_connect"))
    )
    (net (code "66") (name "unconnected-(U14-DB-Pad9)") (class "Default")
      (node (ref "U14") (pin "9") (pinfunction "DB_9") (pintype "passive+no_connect"))
    )
    (net (code "67") (name "unconnected-(U14-S1B-Pad13)") (class "Default")
      (node (ref "U14") (pin "13") (pinfunction "S1B_13") (pintype "passive+no_connect"))
    )
    (net (code "68") (name "unconnected-(U14-S2B-Pad12)") (class "Default")
      (node (ref "U14") (pin "12") (pinfunction "S2B_12") (pintype "passive+no_connect"))
    )
    (net (code "69") (name "unconnected-(U14-S3B-Pad11)") (class "Default")
      (node (ref "U14") (pin "11") (pinfunction "S3B_11") (pintype "passive+no_connect"))
    )
    (net (code "70") (name "unconnected-(U14-S4B-Pad10)") (class "Default")
      (node (ref "U14") (pin "10") (pinfunction "S4B_10") (pintype "passive+no_connect"))
    )
  )
)
